# WIZARD_HV.net
KiCad netlist of a schematic drawn in Altium Designer
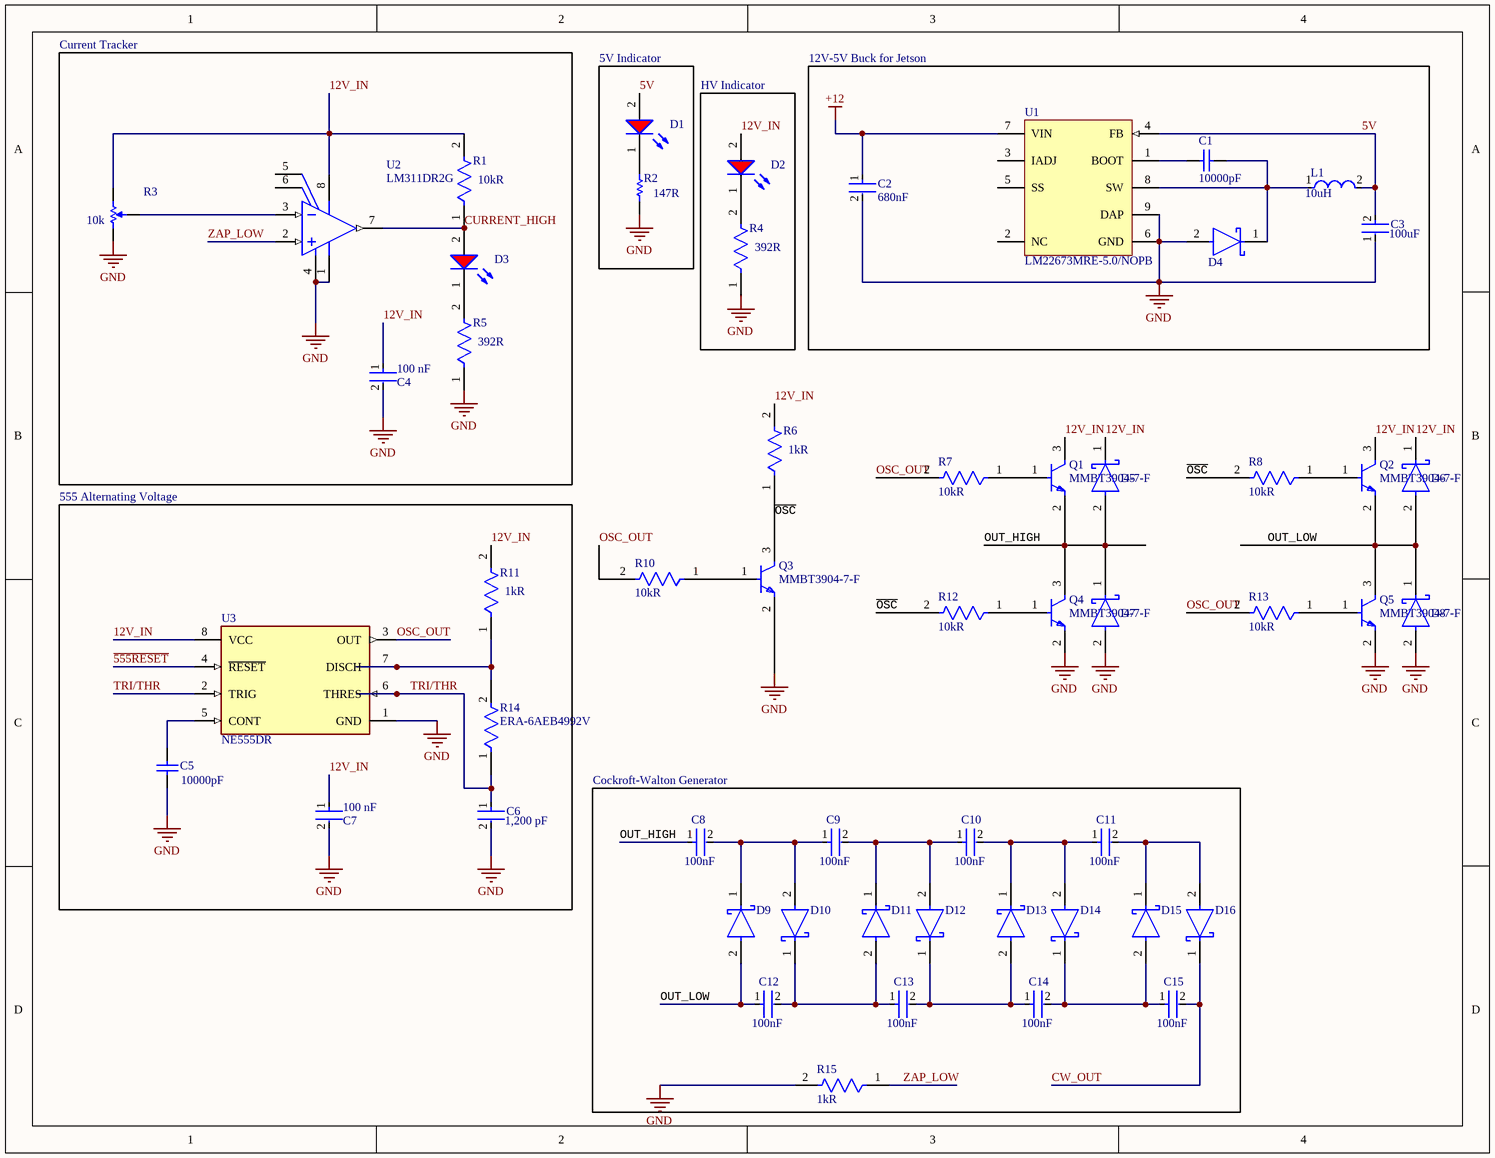
[diagram p0: WIZARD_HV.SchDoc]

(export (version "E")
  (design (tool "Eeschema 10.0.6"))
  (components
    (comp (ref "C1")
      (value "CL21B103KBANNNC")
      (footprint "CAPC2013X75X45LL10T25")
      (description "Multilayer Ceramic Capacitor, 10 nF, 50 V, -55 to 125 degC, 2-Pin SMD, RoHS, Tape and Reel")
      (fields
        (field (name "CAPACITANCE") "10000pF")
        (field (name "MANUFACTURER") "Samsung Electro-Mechanics")
      )
      (libsource (lib "Altium Content Vault") (part "CAP-NP-2"))
    )
    (comp (ref "C2")
      (value "CGA4J3X7R1E684K125AB")
      (footprint "FP-CGA4J-MFG")
      (description "Cap Ceramic 680nF 25V X7R 10% Pad SMD 0805 +125°C Automotive T/R")
      (fields (field (name "CAPACITANCE") "680nF") (field (name "TOLERANCE") "10%"))
      (libsource (lib "Altium Content Vault") (part "b4654b650e69147ec39a6b967a45e02"))
    )
    (comp (ref "C3")
      (value "GRM31CR61A107MEA8L")
      (footprint "FP-GRM31C-0_3-e0_3_0_8-IPC_B")
      (description "Chip Multilayer Ceramic Capacitors for General Purpose, 1206, 100uF, X5R, 15%, 20%, 10V")
      (fields (field (name "PARAMETER 1") "100uF"))
      (libsource (lib "Altium Content Vault") (part "f23184f103b6ebe33a8c269c53dcba6"))
    )
    (comp (ref "C4")
      (value "CC0805KRX7R9BB104")
      (footprint "FP-CC0805-0_85-MFG")
      (description "CAP CER 0.1UF 50V X7R 0805")
      (fields
        (field (name "TOLERANCE") "0.1")
        (field (name "CAPACITANCE") "100 nF")
        (field (name "MANUFACTURER") "Yageo")
      )
      (libsource (lib "Altium Content Vault") (part "11868f565c42a9108669ba33697ecf6"))
    )
    (comp (ref "C5")
      (value "CL21B103KBANNNC")
      (footprint "CAPC2013X75X45LL10T25")
      (description "Multilayer Ceramic Capacitor, 10 nF, 50 V, -55 to 125 degC, 2-Pin SMD, RoHS, Tape and Reel")
      (fields
        (field (name "CAPACITANCE") "10000pF")
        (field (name "MANUFACTURER") "Samsung Electro-Mechanics")
      )
      (libsource (lib "Altium Content Vault") (part "CAP-NP-2"))
    )
    (comp (ref "C6")
      (value "C0805C122K5RACTU")
      (footprint "FP-C0805C-DN-MFG")
      (description "CAP CER 1200PF 50V 10% X7R 0805")
      (fields
        (field (name "TOLERANCE") "0.1")
        (field (name "OCTOPART") "https://octopart.com/c0805c122k5ractu-kemet-8370191")
        (field (name "CAPACITANCE") "1,200 pF")
      )
      (libsource (lib "Altium Content Vault") (part "b4654b650e69147ec39a6b967a45e02"))
    )
    (comp (ref "C7")
      (value "CC0805KRX7R9BB104")
      (footprint "FP-CC0805-0_85-MFG")
      (description "CAP CER 0.1UF 50V X7R 0805")
      (fields
        (field (name "TOLERANCE") "0.1")
        (field (name "CAPACITANCE") "100 nF")
        (field (name "MANUFACTURER") "Yageo")
      )
      (libsource (lib "Altium Content Vault") (part "11868f565c42a9108669ba33697ecf6"))
    )
    (comp (ref "C8")
      (value "C2012X7T2E104K125AA")
      (footprint "FP-C2012-125-0_2-IPC_B")
      (description "Multilayer Ceramic Capacitors 100nF ±10% 250V X7T SMD 0805")
      (fields (field (name "TOLERANCE") "10%") (field (name "CAPACITANCE") "100nF"))
      (libsource (lib "Altium Content Vault") (part "b4654b650e69147ec39a6b967a45e02"))
    )
    (comp (ref "C9")
      (value "C2012X7T2E104K125AA")
      (footprint "FP-C2012-125-0_2-IPC_B")
      (description "Multilayer Ceramic Capacitors 100nF ±10% 250V X7T SMD 0805")
      (fields (field (name "TOLERANCE") "10%") (field (name "CAPACITANCE") "100nF"))
      (libsource (lib "Altium Content Vault") (part "b4654b650e69147ec39a6b967a45e02"))
    )
    (comp (ref "C10")
      (value "C2012X7T2E104K125AA")
      (footprint "FP-C2012-125-0_2-IPC_B")
      (description "Multilayer Ceramic Capacitors 100nF ±10% 250V X7T SMD 0805")
      (fields (field (name "TOLERANCE") "10%") (field (name "CAPACITANCE") "100nF"))
      (libsource (lib "Altium Content Vault") (part "b4654b650e69147ec39a6b967a45e02"))
    )
    (comp (ref "C11")
      (value "C2012X7T2E104K125AA")
      (footprint "FP-C2012-125-0_2-IPC_B")
      (description "Multilayer Ceramic Capacitors 100nF ±10% 250V X7T SMD 0805")
      (fields (field (name "TOLERANCE") "10%") (field (name "CAPACITANCE") "100nF"))
      (libsource (lib "Altium Content Vault") (part "b4654b650e69147ec39a6b967a45e02"))
    )
    (comp (ref "C12")
      (value "C2012X7T2E104K125AA")
      (footprint "FP-C2012-125-0_2-IPC_B")
      (description "Multilayer Ceramic Capacitors 100nF ±10% 250V X7T SMD 0805")
      (fields (field (name "TOLERANCE") "10%") (field (name "CAPACITANCE") "100nF"))
      (libsource (lib "Altium Content Vault") (part "b4654b650e69147ec39a6b967a45e02"))
    )
    (comp (ref "C13")
      (value "C2012X7T2E104K125AA")
      (footprint "FP-C2012-125-0_2-IPC_B")
      (description "Multilayer Ceramic Capacitors 100nF ±10% 250V X7T SMD 0805")
      (fields (field (name "TOLERANCE") "10%") (field (name "CAPACITANCE") "100nF"))
      (libsource (lib "Altium Content Vault") (part "b4654b650e69147ec39a6b967a45e02"))
    )
    (comp (ref "C14")
      (value "C2012X7T2E104K125AA")
      (footprint "FP-C2012-125-0_2-IPC_B")
      (description "Multilayer Ceramic Capacitors 100nF ±10% 250V X7T SMD 0805")
      (fields (field (name "TOLERANCE") "10%") (field (name "CAPACITANCE") "100nF"))
      (libsource (lib "Altium Content Vault") (part "b4654b650e69147ec39a6b967a45e02"))
    )
    (comp (ref "C15")
      (value "C2012X7T2E104K125AA")
      (footprint "FP-C2012-125-0_2-IPC_B")
      (description "Multilayer Ceramic Capacitors 100nF ±10% 250V X7T SMD 0805")
      (fields (field (name "TOLERANCE") "10%") (field (name "CAPACITANCE") "100nF"))
      (libsource (lib "Altium Content Vault") (part "b4654b650e69147ec39a6b967a45e02"))
    )
    (comp (ref "D1")
      (value "150080RS75000")
      (footprint "WL-SMCW_0805_150080xx75000")
      (description "LED Uni-Color Red 630nm 2-Pin Chip 0805(2012Metric) T/R")
      (libsource (lib "Altium Content Vault") (part "LED_Red_2A-1K"))
    )
    (comp (ref "D2")
      (value "150080RS75000")
      (footprint "WL-SMCW_0805_150080xx75000")
      (description "LED Uni-Color Red 630nm 2-Pin Chip 0805(2012Metric) T/R")
      (libsource (lib "Altium Content Vault") (part "LED_Red_2A-1K"))
    )
    (comp (ref "D3")
      (value "150080RS75000")
      (footprint "WL-SMCW_0805_150080xx75000")
      (description "LED Uni-Color Red 630nm 2-Pin Chip 0805(2012Metric) T/R")
      (libsource (lib "Altium Content Vault") (part "LED_Red_2A-1K"))
    )
    (comp (ref "D4")
      (value "SK520B")
      (footprint "FP-SMB-MFG")
      (description "SK520B Diode Schottky 200V 5A Smb")
      (libsource (lib "Altium Content Vault") (part "c1678fac7984e62e0809fbf79c06691"))
    )
    (comp (ref "D5")
      (value "SK520B")
      (footprint "FP-SMB-MFG")
      (description "SK520B Diode Schottky 200V 5A Smb")
      (libsource (lib "Altium Content Vault") (part "c1678fac7984e62e0809fbf79c06691"))
    )
    (comp (ref "D6")
      (value "SK520B")
      (footprint "FP-SMB-MFG")
      (description "SK520B Diode Schottky 200V 5A Smb")
      (libsource (lib "Altium Content Vault") (part "c1678fac7984e62e0809fbf79c06691"))
    )
    (comp (ref "D7")
      (value "SK520B")
      (footprint "FP-SMB-MFG")
      (description "SK520B Diode Schottky 200V 5A Smb")
      (libsource (lib "Altium Content Vault") (part "c1678fac7984e62e0809fbf79c06691"))
    )
    (comp (ref "D8")
      (value "SK520B")
      (footprint "FP-SMB-MFG")
      (description "SK520B Diode Schottky 200V 5A Smb")
      (libsource (lib "Altium Content Vault") (part "c1678fac7984e62e0809fbf79c06691"))
    )
    (comp (ref "D9")
      (value "SK520B")
      (footprint "FP-SMB-MFG")
      (description "SK520B Diode Schottky 200V 5A Smb")
      (libsource (lib "Altium Content Vault") (part "c1678fac7984e62e0809fbf79c06691"))
    )
    (comp (ref "D10")
      (value "SK520B")
      (footprint "FP-SMB-MFG")
      (description "SK520B Diode Schottky 200V 5A Smb")
      (libsource (lib "Altium Content Vault") (part "c1678fac7984e62e0809fbf79c06691"))
    )
    (comp (ref "D11")
      (value "SK520B")
      (footprint "FP-SMB-MFG")
      (description "SK520B Diode Schottky 200V 5A Smb")
      (libsource (lib "Altium Content Vault") (part "c1678fac7984e62e0809fbf79c06691"))
    )
    (comp (ref "D12")
      (value "SK520B")
      (footprint "FP-SMB-MFG")
      (description "SK520B Diode Schottky 200V 5A Smb")
      (libsource (lib "Altium Content Vault") (part "c1678fac7984e62e0809fbf79c06691"))
    )
    (comp (ref "D13")
      (value "SK520B")
      (footprint "FP-SMB-MFG")
      (description "SK520B Diode Schottky 200V 5A Smb")
      (libsource (lib "Altium Content Vault") (part "c1678fac7984e62e0809fbf79c06691"))
    )
    (comp (ref "D14")
      (value "SK520B")
      (footprint "FP-SMB-MFG")
      (description "SK520B Diode Schottky 200V 5A Smb")
      (libsource (lib "Altium Content Vault") (part "c1678fac7984e62e0809fbf79c06691"))
    )
    (comp (ref "D15")
      (value "SK520B")
      (footprint "FP-SMB-MFG")
      (description "SK520B Diode Schottky 200V 5A Smb")
      (libsource (lib "Altium Content Vault") (part "c1678fac7984e62e0809fbf79c06691"))
    )
    (comp (ref "D16")
      (value "SK520B")
      (footprint "FP-SMB-MFG")
      (description "SK520B Diode Schottky 200V 5A Smb")
      (libsource (lib "Altium Content Vault") (part "c1678fac7984e62e0809fbf79c06691"))
    )
    (comp (ref "L1")
      (value "SRP1038A-100M")
      (footprint "FP-SRP1038A-100M-MFG")
      (description "FIXED IND 10UH 7.5A 30 MOHM SMD")
      (fields (field (name "TOLERANCE") "20%") (field (name "INDUCTANCE") "10uH"))
      (libsource (lib "Altium Content Vault") (part "725321dda6339637d4d059423bc1c3c"))
    )
    (comp (ref "Q1")
      (value "MMBT3904-7-F")
      (footprint "FP-SOT23-IPC_A")
      (description "TRANS NPN 40V 0.2A SMD SOT23-3")
      (libsource (lib "Altium Content Vault") (part "b44e953556f554d0102664c7d152cb4"))
    )
    (comp (ref "Q2")
      (value "MMBT3904-7-F")
      (footprint "FP-SOT23-IPC_A")
      (description "TRANS NPN 40V 0.2A SMD SOT23-3")
      (libsource (lib "Altium Content Vault") (part "b44e953556f554d0102664c7d152cb4"))
    )
    (comp (ref "Q3")
      (value "MMBT3904-7-F")
      (footprint "FP-SOT23-IPC_A")
      (description "TRANS NPN 40V 0.2A SMD SOT23-3")
      (libsource (lib "Altium Content Vault") (part "b44e953556f554d0102664c7d152cb4"))
    )
    (comp (ref "Q4")
      (value "MMBT3904-7-F")
      (footprint "FP-SOT23-IPC_A")
      (description "TRANS NPN 40V 0.2A SMD SOT23-3")
      (libsource (lib "Altium Content Vault") (part "b44e953556f554d0102664c7d152cb4"))
    )
    (comp (ref "Q5")
      (value "MMBT3904-7-F")
      (footprint "FP-SOT23-IPC_A")
      (description "TRANS NPN 40V 0.2A SMD SOT23-3")
      (libsource (lib "Altium Content Vault") (part "b44e953556f554d0102664c7d152cb4"))
    )
    (comp (ref "R1")
      (value "RR1220P-103-D")
      (footprint "FP-RR1220-IPC_A")
      (description "10kΩ ±0.5% 0.1W 1/10W Chip Resistor 0805 (2012 Metric) Thin Film")
      (fields (field (name "RESISTANCE") "10kR") (field (name "TOLERANCE") "0.5%"))
      (libsource (lib "Altium Content Vault") (part "1029c3af85768c4190bb7ad29bc67b5"))
    )
    (comp (ref "R2")
      (value "147R")
      (footprint "RESC2013X60X35NL10T20")
      (fields (field (name "MANUFACTURER") "Yageo") (field (name "PART NUMBER") "RC0805FR-07147RL"))
      (libsource (lib "Altium Content Vault") (part "RES"))
    )
    (comp (ref "R3")
      (value "P090S-14T20BR10K")
      (footprint "RES-POT-3")
      (fields
        (field (name "TOLERANCE") "±20%")
        (field (name "MANUFACTURER") "BI Technologies")
        (field (name "RESISTANCE (OHMS)") "10k")
      )
      (libsource (lib "Altium Content Vault") (part "RES-ADJ-3_A"))
    )
    (comp (ref "R4")
      (value "RMCF0805FT392R")
      (footprint "FP-RMCF0805-IPC_A")
      (description "392Ω ±1% 0.125W 0805 Thick Film Chip Resistor AEC-Q200 compliant")
      (fields (field (name "TOLERANCE") "1%") (field (name "RESISTANCE") "392R"))
      (libsource (lib "Altium Content Vault") (part "1029c3af85768c4190bb7ad29bc67b5"))
    )
    (comp (ref "R5")
      (value "RMCF0805FT392R")
      (footprint "FP-RMCF0805-IPC_A")
      (description "392Ω ±1% 0.125W 0805 Thick Film Chip Resistor AEC-Q200 compliant")
      (fields (field (name "TOLERANCE") "1%") (field (name "RESISTANCE") "392R"))
      (libsource (lib "Altium Content Vault") (part "1029c3af85768c4190bb7ad29bc67b5"))
    )
    (comp (ref "R6")
      (value "RR1220P-102-D")
      (footprint "FP-RR1220-IPC_A")
      (description "1kΩ ±0.5% 0.1W 1/10W Chip Resistor 0805 (2012 Metric) Thin Film")
      (fields (field (name "TOLERANCE") "0.5%") (field (name "RESISTANCE") "1kR"))
      (libsource (lib "Altium Content Vault") (part "1029c3af85768c4190bb7ad29bc67b5"))
    )
    (comp (ref "R7")
      (value "RR1220P-103-D")
      (footprint "FP-RR1220-IPC_A")
      (description "10kΩ ±0.5% 0.1W 1/10W Chip Resistor 0805 (2012 Metric) Thin Film")
      (fields (field (name "RESISTANCE") "10kR") (field (name "TOLERANCE") "0.5%"))
      (libsource (lib "Altium Content Vault") (part "1029c3af85768c4190bb7ad29bc67b5"))
    )
    (comp (ref "R8")
      (value "RR1220P-103-D")
      (footprint "FP-RR1220-IPC_A")
      (description "10kΩ ±0.5% 0.1W 1/10W Chip Resistor 0805 (2012 Metric) Thin Film")
      (fields (field (name "RESISTANCE") "10kR") (field (name "TOLERANCE") "0.5%"))
      (libsource (lib "Altium Content Vault") (part "1029c3af85768c4190bb7ad29bc67b5"))
    )
    (comp (ref "R10")
      (value "RR1220P-103-D")
      (footprint "FP-RR1220-IPC_A")
      (description "10kΩ ±0.5% 0.1W 1/10W Chip Resistor 0805 (2012 Metric) Thin Film")
      (fields (field (name "RESISTANCE") "10kR") (field (name "TOLERANCE") "0.5%"))
      (libsource (lib "Altium Content Vault") (part "1029c3af85768c4190bb7ad29bc67b5"))
    )
    (comp (ref "R11")
      (value "RR1220P-102-D")
      (footprint "FP-RR1220-IPC_A")
      (description "1kΩ ±0.5% 0.1W 1/10W Chip Resistor 0805 (2012 Metric) Thin Film")
      (fields (field (name "TOLERANCE") "0.5%") (field (name "RESISTANCE") "1kR"))
      (libsource (lib "Altium Content Vault") (part "1029c3af85768c4190bb7ad29bc67b5"))
    )
    (comp (ref "R12")
      (value "RR1220P-103-D")
      (footprint "FP-RR1220-IPC_A")
      (description "10kΩ ±0.5% 0.1W 1/10W Chip Resistor 0805 (2012 Metric) Thin Film")
      (fields (field (name "RESISTANCE") "10kR") (field (name "TOLERANCE") "0.5%"))
      (libsource (lib "Altium Content Vault") (part "1029c3af85768c4190bb7ad29bc67b5"))
    )
    (comp (ref "R13")
      (value "RR1220P-103-D")
      (footprint "FP-RR1220-IPC_A")
      (description "10kΩ ±0.5% 0.1W 1/10W Chip Resistor 0805 (2012 Metric) Thin Film")
      (fields (field (name "RESISTANCE") "10kR") (field (name "TOLERANCE") "0.5%"))
      (libsource (lib "Altium Content Vault") (part "1029c3af85768c4190bb7ad29bc67b5"))
    )
    (comp (ref "R14")
      (value "ERA-6AEB4992V")
      (footprint "FP-ERA6A_MFG")
      (description "Res Thin Film 0805 49.9K Ohm 0.1% 0.125W(1/8W) +/-25ppm/ßC SMD Automotive T/R")
      (fields (field (name "TOLERANCE") "0.1%"))
      (libsource (lib "Altium Content Vault") (part "ERA-6AEB4992V"))
    )
    (comp (ref "R15")
      (value "RR1220P-102-D")
      (footprint "FP-RR1220-IPC_A")
      (description "1kΩ ±0.5% 0.1W 1/10W Chip Resistor 0805 (2012 Metric) Thin Film")
      (fields (field (name "TOLERANCE") "0.5%") (field (name "RESISTANCE") "1kR"))
      (libsource (lib "Altium Content Vault") (part "1029c3af85768c4190bb7ad29bc67b5"))
    )
    (comp (ref "U1")
      (value "LM22673MRE-5.0/NOPB")
      (footprint "MRA08B_L")
      (fields (field (name "MANUFACTURER") "National Semiconductor"))
      (libsource (lib "Altium Content Vault") (part "PM-REG-LM22673MR"))
    )
    (comp (ref "U2")
      (value "LM311DR2G")
      (footprint "ONSC-SOIC-8-751-07_V")
      (description "Single Comparator, 5 to 30 V, 0 to 70 degC, 8-Pin SOIC, Pb-Free, Tape and Reel")
      (fields (field (name "MANUFACTURER") "On Semiconductor"))
      (libsource (lib "Altium Content Vault") (part "ONSC-LM211_311-8"))
    )
    (comp (ref "U3")
      (value "NE555DR")
      (footprint "FP-D0008A-IPC_A")
      (description "IC OSC SGL TIMER 100KHZ 8-SOIC")
      (libsource (lib "Altium Content Vault") (part "a29bba90211dec1890110b94dad7d53"))
    )
  )
  (nets
    (net (code "1") (name "+12") (class "Default")
      (node (ref "C2") (pin "1") (pinfunction "1_1") (pintype "passive"))
      (node (ref "U1") (pin "7") (pinfunction "VIN_7") (pintype "power_in"))
    )
    (net (code "2") (name "/5V") (class "Default")
      (node (ref "C3") (pin "2") (pinfunction "2_2") (pintype "passive"))
      (node (ref "D1") (pin "2") (pinfunction "A_2") (pintype "passive"))
      (node (ref "L1") (pin "2") (pinfunction "2_2") (pintype "passive"))
      (node (ref "U1") (pin "4") (pinfunction "FB_4") (pintype "input"))
    )
    (net (code "3") (name "/12V_IN") (class "Default")
      (node (ref "C4") (pin "1") (pinfunction "1_1") (pintype "passive"))
      (node (ref "C7") (pin "1") (pinfunction "1_1") (pintype "passive"))
      (node (ref "D2") (pin "2") (pinfunction "A_2") (pintype "passive"))
      (node (ref "D5") (pin "1") (pinfunction "C_1") (pintype "passive"))
      (node (ref "D6") (pin "1") (pinfunction "C_1") (pintype "passive"))
      (node (ref "Q1") (pin "3") (pinfunction "C_3") (pintype "passive"))
      (node (ref "Q2") (pin "3") (pinfunction "C_3") (pintype "passive"))
      (node (ref "R1") (pin "2") (pinfunction "2_2") (pintype "passive"))
      (node (ref "R11") (pin "2") (pinfunction "2_2") (pintype "passive"))
      (node (ref "R3") (pin "3") (pinfunction "3_3") (pintype "passive"))
      (node (ref "R6") (pin "2") (pinfunction "2_2") (pintype "passive"))
      (node (ref "U2") (pin "8") (pinfunction "VCC_8") (pintype "power_in"))
      (node (ref "U3") (pin "8") (pinfunction "VCC_8") (pintype "power_in"))
    )
    (net (code "4") (name "/CURRENT_HIGH") (class "Default")
      (node (ref "D3") (pin "2") (pinfunction "A_2") (pintype "passive"))
      (node (ref "R1") (pin "1") (pinfunction "1_1") (pintype "passive"))
      (node (ref "U2") (pin "7") (pinfunction "OUT_7") (pintype "output"))
    )
    (net (code "5") (name "/CW_OUT") (class "Default")
      (node (ref "C15") (pin "2") (pinfunction "2_2") (pintype "passive"))
      (node (ref "D16") (pin "1") (pinfunction "C_1") (pintype "passive"))
    )
    (net (code "6") (name "/OSC_OUT") (class "Default")
      (node (ref "R10") (pin "2") (pinfunction "2_2") (pintype "passive"))
      (node (ref "R13") (pin "2") (pinfunction "2_2") (pintype "passive"))
      (node (ref "R7") (pin "2") (pinfunction "2_2") (pintype "passive"))
      (node (ref "U3") (pin "3") (pinfunction "OUT_3") (pintype "output"))
    )
    (net (code "7") (name "/OUT_HIGH") (class "Default")
      (node (ref "C8") (pin "1") (pinfunction "1_1") (pintype "passive"))
      (node (ref "D5") (pin "2") (pinfunction "A_2") (pintype "passive"))
      (node (ref "D7") (pin "1") (pinfunction "C_1") (pintype "passive"))
      (node (ref "Q1") (pin "2") (pinfunction "E_2") (pintype "passive"))
      (node (ref "Q4") (pin "3") (pinfunction "C_3") (pintype "passive"))
    )
    (net (code "8") (name "/OUT_LOW") (class "Default")
      (node (ref "C12") (pin "1") (pinfunction "1_1") (pintype "passive"))
      (node (ref "D6") (pin "2") (pinfunction "A_2") (pintype "passive"))
      (node (ref "D8") (pin "1") (pinfunction "C_1") (pintype "passive"))
      (node (ref "D9") (pin "2") (pinfunction "A_2") (pintype "passive"))
      (node (ref "Q2") (pin "2") (pinfunction "E_2") (pintype "passive"))
      (node (ref "Q5") (pin "3") (pinfunction "C_3") (pintype "passive"))
    )
    (net (code "9") (name "/TRI{slash}THR") (class "Default")
      (node (ref "C6") (pin "1") (pinfunction "1_1") (pintype "passive"))
      (node (ref "R14") (pin "1") (pinfunction "1_1") (pintype "passive"))
      (node (ref "U3") (pin "2") (pinfunction "TRIG_2") (pintype "input"))
      (node (ref "U3") (pin "6") (pinfunction "THRES_6") (pintype "input"))
    )
    (net (code "10") (name "/ZAP_LOW") (class "Default")
      (node (ref "R15") (pin "1") (pinfunction "1_1") (pintype "passive"))
      (node (ref "U2") (pin "2") (pinfunction "IN+_2") (pintype "input"))
    )
    (net (code "11") (name "/~{555RESET}") (class "Default")
      (node (ref "U3") (pin "4") (pinfunction "~{RESET}_4") (pintype "input"))
    )
    (net (code "12") (name "/~{OSC}") (class "Default")
      (node (ref "Q3") (pin "3") (pinfunction "C_3") (pintype "passive"))
      (node (ref "R12") (pin "2") (pinfunction "2_2") (pintype "passive"))
      (node (ref "R6") (pin "1") (pinfunction "1_1") (pintype "passive"))
      (node (ref "R8") (pin "2") (pinfunction "2_2") (pintype "passive"))
    )
    (net (code "13") (name "GND") (class "Default")
      (node (ref "C2") (pin "2") (pinfunction "2_2") (pintype "passive"))
      (node (ref "C3") (pin "1") (pinfunction "1_1") (pintype "passive"))
      (node (ref "C4") (pin "2") (pinfunction "2_2") (pintype "passive"))
      (node (ref "C5") (pin "1") (pinfunction "1_1") (pintype "passive"))
      (node (ref "C6") (pin "2") (pinfunction "2_2") (pintype "passive"))
      (node (ref "C7") (pin "2") (pinfunction "2_2") (pintype "passive"))
      (node (ref "D4") (pin "2") (pinfunction "A_2") (pintype "passive"))
      (node (ref "D7") (pin "2") (pinfunction "A_2") (pintype "passive"))
      (node (ref "D8") (pin "2") (pinfunction "A_2") (pintype "passive"))
      (node (ref "Q3") (pin "2") (pinfunction "E_2") (pintype "passive"))
      (node (ref "Q4") (pin "2") (pinfunction "E_2") (pintype "passive"))
      (node (ref "Q5") (pin "2") (pinfunction "E_2") (pintype "passive"))
      (node (ref "R15") (pin "2") (pinfunction "2_2") (pintype "passive"))
      (node (ref "R2") (pin "1") (pinfunction "1_1") (pintype "passive"))
      (node (ref "R3") (pin "1") (pinfunction "1_1") (pintype "passive"))
      (node (ref "R4") (pin "1") (pinfunction "1_1") (pintype "passive"))
      (node (ref "R5") (pin "1") (pinfunction "1_1") (pintype "passive"))
      (node (ref "U1") (pin "6") (pinfunction "GND_6") (pintype "power_in"))
      (node (ref "U1") (pin "9") (pinfunction "DAP_9") (pintype "power_in"))
      (node (ref "U2") (pin "1") (pinfunction "GND_1") (pintype "power_in"))
      (node (ref "U2") (pin "4") (pinfunction "VEE_4") (pintype "power_in"))
      (node (ref "U3") (pin "1") (pinfunction "GND_1") (pintype "power_in"))
    )
    (net (code "14") (name "Net-(D1-K)") (class "Default")
      (node (ref "D1") (pin "1") (pinfunction "K_1") (pintype "passive"))
      (node (ref "R2") (pin "2") (pinfunction "2_2") (pintype "passive"))
    )
    (net (code "15") (name "Net-(D2-K)") (class "Default")
      (node (ref "D2") (pin "1") (pinfunction "K_1") (pintype "passive"))
      (node (ref "R4") (pin "2") (pinfunction "2_2") (pintype "passive"))
    )
    (net (code "16") (name "Net-(D3-K)") (class "Default")
      (node (ref "D3") (pin "1") (pinfunction "K_1") (pintype "passive"))
      (node (ref "R5") (pin "2") (pinfunction "2_2") (pintype "passive"))
    )
    (net (code "17") (name "Net-(D4-C)") (class "Default")
      (node (ref "C1") (pin "1") (pinfunction "1_1") (pintype "passive"))
      (node (ref "D4") (pin "1") (pinfunction "C_1") (pintype "passive"))
      (node (ref "L1") (pin "1") (pinfunction "1_1") (pintype "passive"))
      (node (ref "U1") (pin "8") (pinfunction "SW_8") (pintype "power_in"))
    )
    (net (code "18") (name "Net-(D10-A)") (class "Default")
      (node (ref "C8") (pin "2") (pinfunction "2_2") (pintype "passive"))
      (node (ref "C9") (pin "1") (pinfunction "1_1") (pintype "passive"))
      (node (ref "D10") (pin "2") (pinfunction "A_2") (pintype "passive"))
      (node (ref "D9") (pin "1") (pinfunction "C_1") (pintype "passive"))
    )
    (net (code "19") (name "Net-(D10-C)") (class "Default")
      (node (ref "C12") (pin "2") (pinfunction "2_2") (pintype "passive"))
      (node (ref "C13") (pin "1") (pinfunction "1_1") (pintype "passive"))
      (node (ref "D10") (pin "1") (pinfunction "C_1") (pintype "passive"))
      (node (ref "D11") (pin "2") (pinfunction "A_2") (pintype "passive"))
    )
    (net (code "20") (name "Net-(D11-C)") (class "Default")
      (node (ref "C10") (pin "1") (pinfunction "1_1") (pintype "passive"))
      (node (ref "C9") (pin "2") (pinfunction "2_2") (pintype "passive"))
      (node (ref "D11") (pin "1") (pinfunction "C_1") (pintype "passive"))
      (node (ref "D12") (pin "2") (pinfunction "A_2") (pintype "passive"))
    )
    (net (code "21") (name "Net-(D12-C)") (class "Default")
      (node (ref "C13") (pin "2") (pinfunction "2_2") (pintype "passive"))
      (node (ref "C14") (pin "1") (pinfunction "1_1") (pintype "passive"))
      (node (ref "D12") (pin "1") (pinfunction "C_1") (pintype "passive"))
      (node (ref "D13") (pin "2") (pinfunction "A_2") (pintype "passive"))
    )
    (net (code "22") (name "Net-(D13-C)") (class "Default")
      (node (ref "C10") (pin "2") (pinfunction "2_2") (pintype "passive"))
      (node (ref "C11") (pin "1") (pinfunction "1_1") (pintype "passive"))
      (node (ref "D13") (pin "1") (pinfunction "C_1") (pintype "passive"))
      (node (ref "D14") (pin "2") (pinfunction "A_2") (pintype "passive"))
    )
    (net (code "23") (name "Net-(D14-C)") (class "Default")
      (node (ref "C14") (pin "2") (pinfunction "2_2") (pintype "passive"))
      (node (ref "C15") (pin "1") (pinfunction "1_1") (pintype "passive"))
      (node (ref "D14") (pin "1") (pinfunction "C_1") (pintype "passive"))
      (node (ref "D15") (pin "2") (pinfunction "A_2") (pintype "passive"))
    )
    (net (code "24") (name "Net-(D15-C)") (class "Default")
      (node (ref "C11") (pin "2") (pinfunction "2_2") (pintype "passive"))
      (node (ref "D15") (pin "1") (pinfunction "C_1") (pintype "passive"))
      (node (ref "D16") (pin "2") (pinfunction "A_2") (pintype "passive"))
    )
    (net (code "25") (name "Net-(Q1-B)") (class "Default")
      (node (ref "Q1") (pin "1") (pinfunction "B_1") (pintype "passive"))
      (node (ref "R7") (pin "1") (pinfunction "1_1") (pintype "passive"))
    )
    (net (code "26") (name "Net-(Q2-B)") (class "Default")
      (node (ref "Q2") (pin "1") (pinfunction "B_1") (pintype "passive"))
      (node (ref "R8") (pin "1") (pinfunction "1_1") (pintype "passive"))
    )
    (net (code "27") (name "Net-(Q3-B)") (class "Default")
      (node (ref "Q3") (pin "1") (pinfunction "B_1") (pintype "passive"))
      (node (ref "R10") (pin "1") (pinfunction "1_1") (pintype "passive"))
    )
    (net (code "28") (name "Net-(Q4-B)") (class "Default")
      (node (ref "Q4") (pin "1") (pinfunction "B_1") (pintype "passive"))
      (node (ref "R12") (pin "1") (pinfunction "1_1") (pintype "passive"))
    )
    (net (code "29") (name "Net-(Q5-B)") (class "Default")
      (node (ref "Q5") (pin "1") (pinfunction "B_1") (pintype "passive"))
      (node (ref "R13") (pin "1") (pinfunction "1_1") (pintype "passive"))
    )
    (net (code "30") (name "Net-(U1-BOOT)") (class "Default")
      (node (ref "C1") (pin "2") (pinfunction "2_2") (pintype "passive"))
      (node (ref "U1") (pin "1") (pinfunction "BOOT_1") (pintype "passive"))
    )
    (net (code "31") (name "Net-(U2-IN-)") (class "Default")
      (node (ref "R3") (pin "2") (pinfunction "2_2") (pintype "passive"))
      (node (ref "U2") (pin "3") (pinfunction "IN-_3") (pintype "input"))
    )
    (net (code "32") (name "Net-(U3-CONT)") (class "Default")
      (node (ref "C5") (pin "2") (pinfunction "2_2") (pintype "passive"))
      (node (ref "U3") (pin "5") (pinfunction "CONT_5") (pintype "input"))
    )
    (net (code "33") (name "Net-(U3-DISCH)") (class "Default")
      (node (ref "R11") (pin "1") (pinfunction "1_1") (pintype "passive"))
      (node (ref "R14") (pin "2") (pinfunction "2_2") (pintype "passive"))
      (node (ref "U3") (pin "7") (pinfunction "DISCH_7") (pintype "open_collector"))
    )
    (net (code "34") (name "unconnected-(U1-IADJ-Pad3)") (class "Default")
      (node (ref "U1") (pin "3") (pinfunction "IADJ_3") (pintype "passive"))
    )
    (net (code "35") (name "unconnected-(U1-NC-Pad2)") (class "Default")
      (node (ref "U1") (pin "2") (pinfunction "NC_2") (pintype "passive"))
    )
    (net (code "36") (name "unconnected-(U1-SS-Pad5)") (class "Default")
      (node (ref "U1") (pin "5") (pinfunction "SS_5") (pintype "passive"))
    )
    (net (code "37") (name "unconnected-(U2-BALANCE-Pad5)") (class "Default")
      (node (ref "U2") (pin "5") (pinfunction "BALANCE_5") (pintype "passive"))
    )
    (net (code "38") (name "unconnected-(U2-BALANCE{slash}STROBE-Pad6)") (class "Default")
      (node (ref "U2") (pin "6") (pinfunction "BALANCE/STROBE_6") (pintype "passive"))
    )
  )
)
